# design.net
KiCad netlist of a schematic drawn in EasyEDA Pro
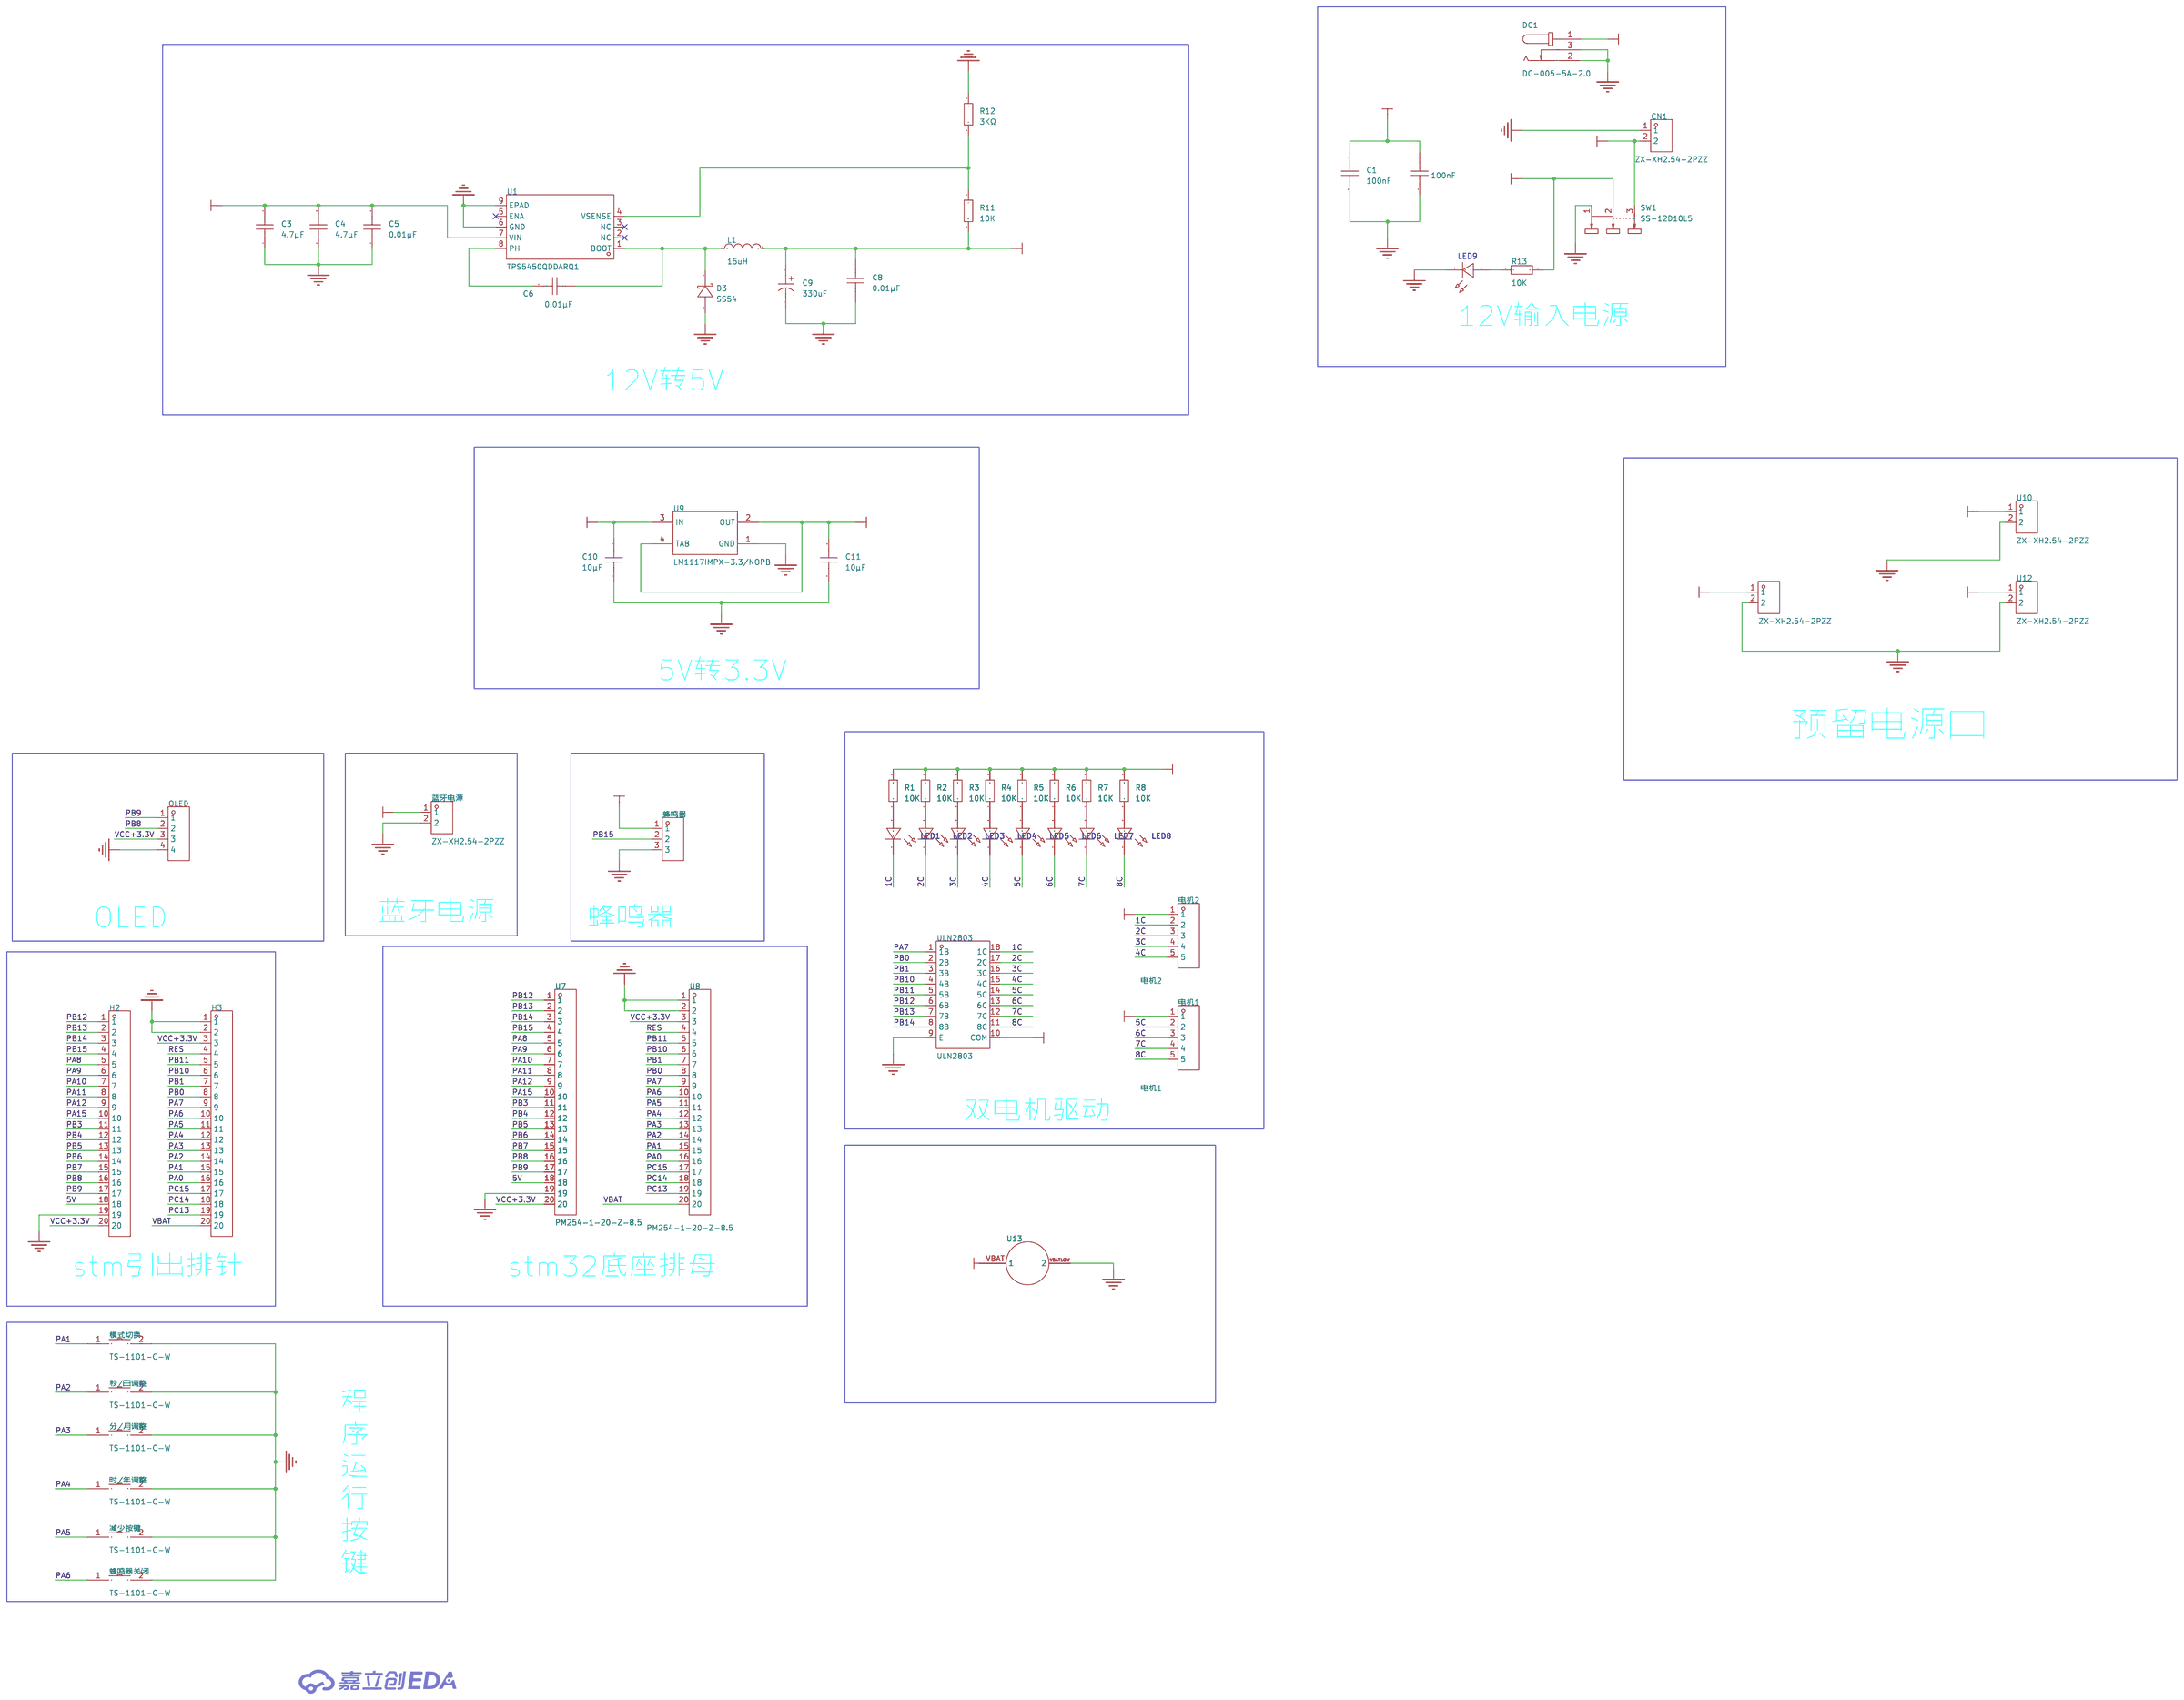
[diagram p0: schematic sheet]

(export (version "E")
  (design (tool "Eeschema 10.0.6"))
  (components
    (comp (ref "C1")
      (value "100nF")
      (footprint "easyedapro:C0603")
      (libsource (lib "easyedapro") (part "CapAcitance"))
    )
    (comp (ref "C2")
      (value "100nF")
      (footprint "easyedapro:C0603")
      (libsource (lib "easyedapro") (part "CapAcitance"))
    )
    (comp (ref "C3")
      (value "4.7μF")
      (footprint "easyedapro:C0603")
      (libsource (lib "easyedapro") (part "CapAcitance"))
    )
    (comp (ref "C4")
      (value "4.7μF")
      (footprint "easyedapro:C0603")
      (libsource (lib "easyedapro") (part "CapAcitance"))
    )
    (comp (ref "C5")
      (value "0.01μF")
      (footprint "easyedapro:C0603")
      (libsource (lib "easyedapro") (part "CapAcitance"))
    )
    (comp (ref "C6")
      (value "0.01μF")
      (footprint "easyedapro:C0603")
      (libsource (lib "easyedapro") (part "CapAcitance"))
    )
    (comp (ref "C8")
      (value "0.01μF")
      (footprint "easyedapro:C0603")
      (libsource (lib "easyedapro") (part "CapAcitance"))
    )
    (comp (ref "C9")
      (value "330uF")
      (footprint "easyedapro:CAP-SMD_BD6.3-L6.6-W6.6-LS7.3-FD")
      (description "容值:330uF;精度:±20%;额定电压:25V;")
      (fields (field (name "Manufacturer Part") "GVM1E331M0607") (field (name "Manufacturer") "HONOR(荣誉)"))
      (libsource (lib "easyedapro") (part "GVM1E331M0607"))
    )
    (comp (ref "C10")
      (value "10μF")
      (footprint "easyedapro:C0603")
      (libsource (lib "easyedapro") (part "CapAcitance"))
    )
    (comp (ref "C11")
      (value "10μF")
      (footprint "easyedapro:C0603")
      (libsource (lib "easyedapro") (part "CapAcitance"))
    )
    (comp (ref "CN1")
      (value "ZX-XH2.54-2PZZ")
      (footprint "easyedapro:CONN-TH_2P-P2.50_HX25003-2A")
      (fields (field (name "Manufacturer") "Megastar(兆星)"))
      (libsource (lib "easyedapro") (part "ZX-XH2.54-2PZZ"))
    )
    (comp (ref "D3")
      (value "SS54")
      (footprint "easyedapro:SMA_L4.3-W2.6-LS5.0-FD")
      (description "二极管配置:独立式;正向压降(Vf):550mV@5.0A;直流反向耐压(Vr):40V;整流电流:5A;")
      (fields (field (name "Manufacturer") "宏迦橙"))
      (libsource (lib "easyedapro") (part "SS54_C7420369"))
    )
    (comp (ref "DC1")
      (value "DC-005-5A-2.0")
      (footprint "easyedapro:DC-IN-TH_DC-005-5A-2.0")
      (description "连接器类型:DC电源插座;安装方式:弯插;触点内径:2mm;触点外径:6.2mm;额定电流:5A;额定电压:24V;工作温度范围:-20°C~+70°C;")
      (fields (field (name "Manufacturer") "XKB Connection(中国星坤)"))
      (libsource (lib "easyedapro") (part "DC-005-5A-2.0"))
    )
    (comp (ref "H2")
      (value "~")
      (footprint "easyedapro:HDR-TH_20P-P2.54-V-M-1")
      (libsource (lib "easyedapro") (part "HDR_2.54-1x20P"))
    )
    (comp (ref "H3")
      (value "~")
      (footprint "easyedapro:HDR-TH_20P-P2.54-V-M-1")
      (libsource (lib "easyedapro") (part "HDR_2.54-1x20P"))
    )
    (comp (ref "L1")
      (value "15uH")
      (footprint "easyedapro:IND-SMD_L7.0-W6.6_FXL0630")
      (description "电感值:15uH;精度:±20%;额定电流:3A;饱和电流(Isat):4.5A;类型:一体成型电感;")
      (fields (field (name "Manufacturer Part") "FXL0630-150-M") (field (name "Manufacturer") "cjiang(长江微电)"))
      (libsource (lib "easyedapro") (part "FXL0630-150-M"))
    )
    (comp (ref "LED1")
      (value "~")
      (footprint "easyedapro:LED_0603")
      (libsource (lib "easyedapro") (part "LED_G"))
    )
    (comp (ref "LED2")
      (value "~")
      (footprint "easyedapro:LED_0603")
      (libsource (lib "easyedapro") (part "LED_G"))
    )
    (comp (ref "LED3")
      (value "~")
      (footprint "easyedapro:LED_0603")
      (libsource (lib "easyedapro") (part "LED_G"))
    )
    (comp (ref "LED4")
      (value "~")
      (footprint "easyedapro:LED_0603")
      (libsource (lib "easyedapro") (part "LED_G"))
    )
    (comp (ref "LED5")
      (value "~")
      (footprint "easyedapro:LED_0603")
      (libsource (lib "easyedapro") (part "LED_G"))
    )
    (comp (ref "LED6")
      (value "~")
      (footprint "easyedapro:LED_0603")
      (libsource (lib "easyedapro") (part "LED_G"))
    )
    (comp (ref "LED7")
      (value "~")
      (footprint "easyedapro:LED_0603")
      (libsource (lib "easyedapro") (part "LED_G"))
    )
    (comp (ref "LED8")
      (value "~")
      (footprint "easyedapro:LED_0603")
      (libsource (lib "easyedapro") (part "LED_G"))
    )
    (comp (ref "LED9")
      (value "~")
      (footprint "easyedapro:LED_0603")
      (libsource (lib "easyedapro") (part "LED_G"))
    )
    (comp (ref "OLED")
      (value "~")
      (footprint "easyedapro:HDR-TH_4P-P2.54-V-F")
      (libsource (lib "easyedapro") (part "2.54-1*4P母"))
    )
    (comp (ref "R1") (value "10K") (footprint "easyedapro:R0603") (libsource (lib "easyedapro") (part "电阻")))
    (comp (ref "R2") (value "10K") (footprint "easyedapro:R0603") (libsource (lib "easyedapro") (part "电阻")))
    (comp (ref "R3") (value "10K") (footprint "easyedapro:R0603") (libsource (lib "easyedapro") (part "电阻")))
    (comp (ref "R4") (value "10K") (footprint "easyedapro:R0603") (libsource (lib "easyedapro") (part "电阻")))
    (comp (ref "R5") (value "10K") (footprint "easyedapro:R0603") (libsource (lib "easyedapro") (part "电阻")))
    (comp (ref "R6") (value "10K") (footprint "easyedapro:R0603") (libsource (lib "easyedapro") (part "电阻")))
    (comp (ref "R7") (value "10K") (footprint "easyedapro:R0603") (libsource (lib "easyedapro") (part "电阻")))
    (comp (ref "R8") (value "10K") (footprint "easyedapro:R0603") (libsource (lib "easyedapro") (part "电阻")))
    (comp (ref "R11") (value "10K") (footprint "easyedapro:R0603") (libsource (lib "easyedapro") (part "电阻")))
    (comp (ref "R12") (value "3KΩ") (footprint "easyedapro:R0603") (libsource (lib "easyedapro") (part "电阻")))
    (comp (ref "R13") (value "10K") (footprint "easyedapro:R0603") (libsource (lib "easyedapro") (part "电阻")))
    (comp (ref "SW1")
      (value "SS-12D10L5")
      (footprint "easyedapro:SW-TH_SS-12D10L5")
      (description "电路结构:单刀双掷;安装方式:直插;开关颜色:黑色;额定电流(DC):3A;额定电压(DC):125V;额定电流(AC):3A;额定电压(AC):125V;机械寿命:1万次;")
      (fields (field (name "Manufacturer") "XKB Connectivity(中国星坤)"))
      (libsource (lib "easyedapro") (part "SS-12D10L5"))
    )
    (comp (ref "U1")
      (value "TPS5450QDDARQ1")
      (footprint "easyedapro:SOIC-8_L4.9-W3.9-P1.27-LS6.0-BL-EP")
      (description "功能类型:降压型;输出类型:可调;工作电压:5.5V~36V;输出电压:1.221V~32.04V;输出电流:5A;")
      (fields (field (name "Manufacturer") "TI(德州仪器)"))
      (libsource (lib "easyedapro") (part "TPS5450QDDARQ1"))
    )
    (comp (ref "U7")
      (value "PM254-1-20-Z-8.5")
      (footprint "easyedapro:HDR-TH_20P-P2.54-V-F-2")
      (fields (field (name "Manufacturer") "HCTL(华灿天禄)"))
      (libsource (lib "easyedapro") (part "PM254-1-20-Z-8.5"))
    )
    (comp (ref "U8")
      (value "PM254-1-20-Z-8.5")
      (footprint "easyedapro:HDR-TH_20P-P2.54-V-F-2")
      (fields (field (name "Manufacturer") "HCTL(华灿天禄)"))
      (libsource (lib "easyedapro") (part "PM254-1-20-Z-8.5"))
    )
    (comp (ref "U9")
      (value "LM1117IMPX-3.3/NOPB")
      (footprint "easyedapro:SOT-223_L6.5-W3.5-P2.30-LS7.0-BR")
      (description "输出类型:固定;最大输入电压:15V;输出电压:3.3V;最大输出电流:800mA;电源纹波抑制比(PSRR):75dB@(120Hz);输出极性:正极;")
      (fields (field (name "Manufacturer") "TI(德州仪器)"))
      (libsource (lib "easyedapro") (part "LM1117IMPX-3.3/NOPB"))
    )
    (comp (ref "U10")
      (value "ZX-XH2.54-2PZZ")
      (footprint "easyedapro:CONN-TH_2P-P2.50_HX25003-2A")
      (fields (field (name "Manufacturer") "Megastar(兆星)"))
      (libsource (lib "easyedapro") (part "ZX-XH2.54-2PZZ"))
    )
    (comp (ref "U11")
      (value "ZX-XH2.54-2PZZ")
      (footprint "easyedapro:CONN-TH_2P-P2.50_HX25003-2A")
      (fields (field (name "Manufacturer") "Megastar(兆星)"))
      (libsource (lib "easyedapro") (part "ZX-XH2.54-2PZZ"))
    )
    (comp (ref "U12")
      (value "ZX-XH2.54-2PZZ")
      (footprint "easyedapro:CONN-TH_2P-P2.50_HX25003-2A")
      (fields (field (name "Manufacturer") "Megastar(兆星)"))
      (libsource (lib "easyedapro") (part "ZX-XH2.54-2PZZ"))
    )
    (comp (ref "U13") (value "~") (libsource (lib "easyedapro") (part "纽扣")))
    (comp (ref "ULN2803")
      (value "ULN2803")
      (footprint "easyedapro:SOP-18_L11.6-W7.5-P1.27-LS10.3-BL")
      (description "通道数:八路;集射击穿电压(Vceo):50V;集电极电流(Ic):500mA;")
      (fields (field (name "Manufacturer") "Siproin(上海矽朋)"))
      (libsource (lib "easyedapro") (part "ULN2803_C2758014"))
    )
    (comp (ref "减少按键")
      (value "TS-1101-C-W")
      (footprint "easyedapro:SW-SMD_L6.0-W3.3-LS8.0")
      (fields (field (name "Manufacturer") "XKB Connectivity(中国星坤)"))
      (libsource (lib "easyedapro") (part "TS-1101-C-W"))
    )
    (comp (ref "分/月调整")
      (value "TS-1101-C-W")
      (footprint "easyedapro:SW-SMD_L6.0-W3.3-LS8.0")
      (fields (field (name "Manufacturer") "XKB Connectivity(中国星坤)"))
      (libsource (lib "easyedapro") (part "TS-1101-C-W"))
    )
    (comp (ref "时/年调整")
      (value "TS-1101-C-W")
      (footprint "easyedapro:SW-SMD_L6.0-W3.3-LS8.0")
      (fields (field (name "Manufacturer") "XKB Connectivity(中国星坤)"))
      (libsource (lib "easyedapro") (part "TS-1101-C-W"))
    )
    (comp (ref "模式切换")
      (value "TS-1101-C-W")
      (footprint "easyedapro:SW-SMD_L6.0-W3.3-LS8.0")
      (fields (field (name "Manufacturer") "XKB Connectivity(中国星坤)"))
      (libsource (lib "easyedapro") (part "TS-1101-C-W"))
    )
    (comp (ref "电机1")
      (value "电机1")
      (footprint "easyedapro:CONN-TH_5P-P2.50_ZX-XH2.54-5PZZ")
      (fields (field (name "Manufacturer") "Megastar(兆星)"))
      (libsource (lib "easyedapro") (part "ZX-XH2.54-5PZZ"))
    )
    (comp (ref "电机2")
      (value "电机2")
      (footprint "easyedapro:CONN-TH_5P-P2.50_ZX-XH2.54-5PZZ")
      (fields (field (name "Manufacturer") "Megastar(兆星)"))
      (libsource (lib "easyedapro") (part "ZX-XH2.54-5PZZ"))
    )
    (comp (ref "秒/日调整")
      (value "TS-1101-C-W")
      (footprint "easyedapro:SW-SMD_L6.0-W3.3-LS8.0")
      (fields (field (name "Manufacturer") "XKB Connectivity(中国星坤)"))
      (libsource (lib "easyedapro") (part "TS-1101-C-W"))
    )
    (comp (ref "蓝牙电源")
      (value "ZX-XH2.54-2PZZ")
      (footprint "easyedapro:CONN-TH_2P-P2.50_HX25003-2A")
      (fields (field (name "Manufacturer") "Megastar(兆星)"))
      (libsource (lib "easyedapro") (part "ZX-XH2.54-2PZZ"))
    )
    (comp (ref "蜂鸣器")
      (value "~")
      (footprint "easyedapro:HDR-TH_3P-P2.54-V-F")
      (libsource (lib "easyedapro") (part "PM254V-11-03-H85"))
    )
    (comp (ref "蜂鸣器关闭")
      (value "TS-1101-C-W")
      (footprint "easyedapro:SW-SMD_L6.0-W3.3-LS8.0")
      (fields (field (name "Manufacturer") "XKB Connectivity(中国星坤)"))
      (libsource (lib "easyedapro") (part "TS-1101-C-W"))
    )
  )
  (nets
    (net (code "1") (name "/1C") (class "Default")
      (node (ref "LED1") (pin "1") (pinfunction "C_1") (pintype "input"))
      (node (ref "ULN2803") (pin "18") (pinfunction "1C_18") (pintype "unspecified"))
      (node (ref "电机2") (pin "2") (pinfunction "2_2") (pintype "unspecified"))
    )
    (net (code "2") (name "/2C") (class "Default")
      (node (ref "LED2") (pin "1") (pinfunction "C_1") (pintype "input"))
      (node (ref "ULN2803") (pin "17") (pinfunction "2C_17") (pintype "unspecified"))
      (node (ref "电机2") (pin "3") (pinfunction "3_3") (pintype "unspecified"))
    )
    (net (code "3") (name "/3C") (class "Default")
      (node (ref "LED3") (pin "1") (pinfunction "C_1") (pintype "input"))
      (node (ref "ULN2803") (pin "16") (pinfunction "3C_16") (pintype "unspecified"))
      (node (ref "电机2") (pin "4") (pinfunction "4_4") (pintype "unspecified"))
    )
    (net (code "4") (name "/4C") (class "Default")
      (node (ref "LED4") (pin "1") (pinfunction "C_1") (pintype "input"))
      (node (ref "ULN2803") (pin "15") (pinfunction "4C_15") (pintype "unspecified"))
      (node (ref "电机2") (pin "5") (pinfunction "5_5") (pintype "unspecified"))
    )
    (net (code "5") (name "/5C") (class "Default")
      (node (ref "LED5") (pin "1") (pinfunction "C_1") (pintype "input"))
      (node (ref "ULN2803") (pin "14") (pinfunction "5C_14") (pintype "unspecified"))
      (node (ref "电机1") (pin "2") (pinfunction "2_2") (pintype "unspecified"))
    )
    (net (code "6") (name "/5V") (class "Default")
      (node (ref "H2") (pin "18") (pinfunction "18_18") (pintype "input"))
      (node (ref "U7") (pin "18") (pinfunction "18_18") (pintype "unspecified"))
    )
    (net (code "7") (name "/6C") (class "Default")
      (node (ref "LED6") (pin "1") (pinfunction "C_1") (pintype "input"))
      (node (ref "ULN2803") (pin "13") (pinfunction "6C_13") (pintype "unspecified"))
      (node (ref "电机1") (pin "3") (pinfunction "3_3") (pintype "unspecified"))
    )
    (net (code "8") (name "/7C") (class "Default")
      (node (ref "LED7") (pin "1") (pinfunction "C_1") (pintype "input"))
      (node (ref "ULN2803") (pin "12") (pinfunction "7C_12") (pintype "unspecified"))
      (node (ref "电机1") (pin "4") (pinfunction "4_4") (pintype "unspecified"))
    )
    (net (code "9") (name "/8C") (class "Default")
      (node (ref "LED8") (pin "1") (pinfunction "C_1") (pintype "input"))
      (node (ref "ULN2803") (pin "11") (pinfunction "8C_11") (pintype "unspecified"))
      (node (ref "电机1") (pin "5") (pinfunction "5_5") (pintype "unspecified"))
    )
    (net (code "10") (name "/PA0") (class "Default")
      (node (ref "H3") (pin "16") (pinfunction "16_16") (pintype "input"))
      (node (ref "U8") (pin "16") (pinfunction "16_16") (pintype "unspecified"))
    )
    (net (code "11") (name "/PA1") (class "Default")
      (node (ref "H3") (pin "15") (pinfunction "15_15") (pintype "input"))
      (node (ref "U8") (pin "15") (pinfunction "15_15") (pintype "unspecified"))
      (node (ref "模式切换") (pin "1") (pinfunction "1_1") (pintype "unspecified"))
    )
    (net (code "12") (name "/PA2") (class "Default")
      (node (ref "H3") (pin "14") (pinfunction "14_14") (pintype "input"))
      (node (ref "U8") (pin "14") (pinfunction "14_14") (pintype "unspecified"))
      (node (ref "秒/日调整") (pin "1") (pinfunction "1_1") (pintype "unspecified"))
    )
    (net (code "13") (name "/PA3") (class "Default")
      (node (ref "H3") (pin "13") (pinfunction "13_13") (pintype "input"))
      (node (ref "U8") (pin "13") (pinfunction "13_13") (pintype "unspecified"))
      (node (ref "分/月调整") (pin "1") (pinfunction "1_1") (pintype "unspecified"))
    )
    (net (code "14") (name "/PA4") (class "Default")
      (node (ref "H3") (pin "12") (pinfunction "12_12") (pintype "input"))
      (node (ref "U8") (pin "12") (pinfunction "12_12") (pintype "unspecified"))
      (node (ref "时/年调整") (pin "1") (pinfunction "1_1") (pintype "unspecified"))
    )
    (net (code "15") (name "/PA5") (class "Default")
      (node (ref "H3") (pin "11") (pinfunction "11_11") (pintype "input"))
      (node (ref "U8") (pin "11") (pinfunction "11_11") (pintype "unspecified"))
      (node (ref "减少按键") (pin "1") (pinfunction "1_1") (pintype "unspecified"))
    )
    (net (code "16") (name "/PA6") (class "Default")
      (node (ref "H3") (pin "10") (pinfunction "10_10") (pintype "input"))
      (node (ref "U8") (pin "10") (pinfunction "10_10") (pintype "unspecified"))
      (node (ref "蜂鸣器关闭") (pin "1") (pinfunction "1_1") (pintype "unspecified"))
    )
    (net (code "17") (name "/PA7") (class "Default")
      (node (ref "H3") (pin "9") (pinfunction "9_9") (pintype "input"))
      (node (ref "U8") (pin "9") (pinfunction "9_9") (pintype "unspecified"))
      (node (ref "ULN2803") (pin "1") (pinfunction "1B_1") (pintype "unspecified"))
    )
    (net (code "18") (name "/PA8") (class "Default")
      (node (ref "H2") (pin "5") (pinfunction "5_5") (pintype "input"))
      (node (ref "U7") (pin "5") (pinfunction "5_5") (pintype "unspecified"))
    )
    (net (code "19") (name "/PA9") (class "Default")
      (node (ref "H2") (pin "6") (pinfunction "6_6") (pintype "input"))
      (node (ref "U7") (pin "6") (pinfunction "6_6") (pintype "unspecified"))
    )
    (net (code "20") (name "/PA10") (class "Default")
      (node (ref "H2") (pin "7") (pinfunction "7_7") (pintype "input"))
      (node (ref "U7") (pin "7") (pinfunction "7_7") (pintype "unspecified"))
    )
    (net (code "21") (name "/PA11") (class "Default")
      (node (ref "H2") (pin "8") (pinfunction "8_8") (pintype "input"))
      (node (ref "U7") (pin "8") (pinfunction "8_8") (pintype "unspecified"))
    )
    (net (code "22") (name "/PA12") (class "Default")
      (node (ref "H2") (pin "9") (pinfunction "9_9") (pintype "input"))
      (node (ref "U7") (pin "9") (pinfunction "9_9") (pintype "unspecified"))
    )
    (net (code "23") (name "/PA15") (class "Default")
      (node (ref "H2") (pin "10") (pinfunction "10_10") (pintype "input"))
      (node (ref "U7") (pin "10") (pinfunction "10_10") (pintype "unspecified"))
    )
    (net (code "24") (name "/PB0") (class "Default")
      (node (ref "H3") (pin "8") (pinfunction "8_8") (pintype "input"))
      (node (ref "U8") (pin "8") (pinfunction "8_8") (pintype "unspecified"))
      (node (ref "ULN2803") (pin "2") (pinfunction "2B_2") (pintype "unspecified"))
    )
    (net (code "25") (name "/PB1") (class "Default")
      (node (ref "H3") (pin "7") (pinfunction "7_7") (pintype "input"))
      (node (ref "U8") (pin "7") (pinfunction "7_7") (pintype "unspecified"))
      (node (ref "ULN2803") (pin "3") (pinfunction "3B_3") (pintype "unspecified"))
    )
    (net (code "26") (name "/PB3") (class "Default")
      (node (ref "H2") (pin "11") (pinfunction "11_11") (pintype "input"))
      (node (ref "U7") (pin "11") (pinfunction "11_11") (pintype "unspecified"))
    )
    (net (code "27") (name "/PB4") (class "Default")
      (node (ref "H2") (pin "12") (pinfunction "12_12") (pintype "input"))
      (node (ref "U7") (pin "12") (pinfunction "12_12") (pintype "unspecified"))
    )
    (net (code "28") (name "/PB5") (class "Default")
      (node (ref "H2") (pin "13") (pinfunction "13_13") (pintype "input"))
      (node (ref "U7") (pin "13") (pinfunction "13_13") (pintype "unspecified"))
    )
    (net (code "29") (name "/PB6") (class "Default")
      (node (ref "H2") (pin "14") (pinfunction "14_14") (pintype "input"))
      (node (ref "U7") (pin "14") (pinfunction "14_14") (pintype "unspecified"))
    )
    (net (code "30") (name "/PB7") (class "Default")
      (node (ref "H2") (pin "15") (pinfunction "15_15") (pintype "input"))
      (node (ref "U7") (pin "15") (pinfunction "15_15") (pintype "unspecified"))
    )
    (net (code "31") (name "/PB8") (class "Default")
      (node (ref "H2") (pin "16") (pinfunction "16_16") (pintype "input"))
      (node (ref "OLED") (pin "2") (pinfunction "2_2") (pintype "unspecified"))
      (node (ref "U7") (pin "16") (pinfunction "16_16") (pintype "unspecified"))
    )
    (net (code "32") (name "/PB9") (class "Default")
      (node (ref "H2") (pin "17") (pinfunction "17_17") (pintype "input"))
      (node (ref "OLED") (pin "1") (pinfunction "1_1") (pintype "unspecified"))
      (node (ref "U7") (pin "17") (pinfunction "17_17") (pintype "unspecified"))
    )
    (net (code "33") (name "/PB10") (class "Default")
      (node (ref "H3") (pin "6") (pinfunction "6_6") (pintype "input"))
      (node (ref "U8") (pin "6") (pinfunction "6_6") (pintype "unspecified"))
      (node (ref "ULN2803") (pin "4") (pinfunction "4B_4") (pintype "unspecified"))
    )
    (net (code "34") (name "/PB11") (class "Default")
      (node (ref "H3") (pin "5") (pinfunction "5_5") (pintype "input"))
      (node (ref "U8") (pin "5") (pinfunction "5_5") (pintype "unspecified"))
      (node (ref "ULN2803") (pin "5") (pinfunction "5B_5") (pintype "unspecified"))
    )
    (net (code "35") (name "/PB12") (class "Default")
      (node (ref "H2") (pin "1") (pinfunction "1_1") (pintype "input"))
      (node (ref "U7") (pin "1") (pinfunction "1_1") (pintype "unspecified"))
      (node (ref "ULN2803") (pin "6") (pinfunction "6B_6") (pintype "unspecified"))
    )
    (net (code "36") (name "/PB13") (class "Default")
      (node (ref "H2") (pin "2") (pinfunction "2_2") (pintype "input"))
      (node (ref "U7") (pin "2") (pinfunction "2_2") (pintype "unspecified"))
      (node (ref "ULN2803") (pin "7") (pinfunction "7B_7") (pintype "unspecified"))
    )
    (net (code "37") (name "/PB14") (class "Default")
      (node (ref "H2") (pin "3") (pinfunction "3_3") (pintype "input"))
      (node (ref "U7") (pin "3") (pinfunction "3_3") (pintype "unspecified"))
      (node (ref "ULN2803") (pin "8") (pinfunction "8B_8") (pintype "unspecified"))
    )
    (net (code "38") (name "/PB15") (class "Default")
      (node (ref "H2") (pin "4") (pinfunction "4_4") (pintype "input"))
      (node (ref "U7") (pin "4") (pinfunction "4_4") (pintype "unspecified"))
      (node (ref "蜂鸣器") (pin "2") (pinfunction "2_2") (pintype "unspecified"))
    )
    (net (code "39") (name "/PC13") (class "Default")
      (node (ref "H3") (pin "19") (pinfunction "19_19") (pintype "input"))
      (node (ref "U8") (pin "19") (pinfunction "19_19") (pintype "unspecified"))
    )
    (net (code "40") (name "/PC14") (class "Default")
      (node (ref "H3") (pin "18") (pinfunction "18_18") (pintype "input"))
      (node (ref "U8") (pin "18") (pinfunction "18_18") (pintype "unspecified"))
    )
    (net (code "41") (name "/PC15") (class "Default")
      (node (ref "H3") (pin "17") (pinfunction "17_17") (pintype "input"))
      (node (ref "U8") (pin "17") (pinfunction "17_17") (pintype "unspecified"))
    )
    (net (code "42") (name "/RES") (class "Default")
      (node (ref "H3") (pin "4") (pinfunction "4_4") (pintype "input"))
      (node (ref "U8") (pin "4") (pinfunction "4_4") (pintype "unspecified"))
    )
    (net (code "43") (name "GND") (class "Default")
      (node (ref "C1") (pin "2") (pinfunction "2_2") (pintype "input"))
      (node (ref "C10") (pin "2") (pinfunction "2_2") (pintype "input"))
      (node (ref "C11") (pin "1") (pinfunction "1_1") (pintype "input"))
      (node (ref "C2") (pin "2") (pinfunction "2_2") (pintype "input"))
      (node (ref "C3") (pin "1") (pinfunction "1_1") (pintype "input"))
      (node (ref "C4") (pin "1") (pinfunction "1_1") (pintype "input"))
      (node (ref "C5") (pin "1") (pinfunction "1_1") (pintype "input"))
      (node (ref "C8") (pin "1") (pinfunction "1_1") (pintype "input"))
      (node (ref "C9") (pin "2") (pinfunction "2_2") (pintype "input"))
      (node (ref "CN1") (pin "1") (pinfunction "1_1") (pintype "unspecified"))
      (node (ref "D3") (pin "1") (pinfunction "A_1") (pintype "unspecified"))
      (node (ref "DC1") (pin "2") (pinfunction "2_2") (pintype "unspecified"))
      (node (ref "DC1") (pin "3") (pinfunction "3_3") (pintype "unspecified"))
      (node (ref "H2") (pin "19") (pinfunction "19_19") (pintype "input"))
      (node (ref "H3") (pin "1") (pinfunction "1_1") (pintype "input"))
      (node (ref "H3") (pin "2") (pinfunction "2_2") (pintype "input"))
      (node (ref "LED9") (pin "1") (pinfunction "C_1") (pintype "input"))
      (node (ref "OLED") (pin "4") (pinfunction "4_4") (pintype "unspecified"))
      (node (ref "R12") (pin "1") (pinfunction "1_1") (pintype "input"))
      (node (ref "SW1") (pin "1") (pinfunction "1_1") (pintype "unspecified"))
      (node (ref "U1") (pin "6") (pinfunction "GND_6") (pintype "unspecified"))
      (node (ref "U1") (pin "9") (pinfunction "EPAD_9") (pintype "unspecified"))
      (node (ref "U10") (pin "2") (pinfunction "2_2") (pintype "unspecified"))
      (node (ref "U11") (pin "2") (pinfunction "2_2") (pintype "unspecified"))
      (node (ref "U12") (pin "2") (pinfunction "2_2") (pintype "unspecified"))
      (node (ref "U13") (pin "VBATLOW") (pinfunction "2_VBATLOW") (pintype "input"))
      (node (ref "U7") (pin "19") (pinfunction "19_19") (pintype "unspecified"))
      (node (ref "U8") (pin "1") (pinfunction "1_1") (pintype "unspecified"))
      (node (ref "U8") (pin "2") (pinfunction "2_2") (pintype "unspecified"))
      (node (ref "U9") (pin "1") (pinfunction "GND_1") (pintype "unspecified"))
      (node (ref "ULN2803") (pin "9") (pinfunction "E_9") (pintype "unspecified"))
      (node (ref "减少按键") (pin "2") (pinfunction "2_2") (pintype "unspecified"))
      (node (ref "分/月调整") (pin "2") (pinfunction "2_2") (pintype "unspecified"))
      (node (ref "时/年调整") (pin "2") (pinfunction "2_2") (pintype "unspecified"))
      (node (ref "模式切换") (pin "2") (pinfunction "2_2") (pintype "unspecified"))
      (node (ref "秒/日调整") (pin "2") (pinfunction "2_2") (pintype "unspecified"))
      (node (ref "蓝牙电源") (pin "2") (pinfunction "2_2") (pintype "unspecified"))
      (node (ref "蜂鸣器") (pin "3") (pinfunction "3_3") (pintype "unspecified"))
      (node (ref "蜂鸣器关闭") (pin "2") (pinfunction "2_2") (pintype "unspecified"))
    )
    (net (code "44") (name "Net-(D3-K)") (class "Default")
      (node (ref "C6") (pin "2") (pinfunction "2_2") (pintype "input"))
      (node (ref "D3") (pin "2") (pinfunction "K_2") (pintype "unspecified"))
      (node (ref "L1") (pin "1") (pinfunction "1_1") (pintype "unspecified"))
      (node (ref "U1") (pin "1") (pinfunction "BOOT_1") (pintype "unspecified"))
    )
    (net (code "45") (name "Net-(LED1-A)") (class "Default")
      (node (ref "LED1") (pin "2") (pinfunction "A_2") (pintype "input"))
      (node (ref "R1") (pin "1") (pinfunction "1_1") (pintype "input"))
    )
    (net (code "46") (name "Net-(LED2-A)") (class "Default")
      (node (ref "LED2") (pin "2") (pinfunction "A_2") (pintype "input"))
      (node (ref "R2") (pin "1") (pinfunction "1_1") (pintype "input"))
    )
    (net (code "47") (name "Net-(LED3-A)") (class "Default")
      (node (ref "LED3") (pin "2") (pinfunction "A_2") (pintype "input"))
      (node (ref "R3") (pin "1") (pinfunction "1_1") (pintype "input"))
    )
    (net (code "48") (name "Net-(LED4-A)") (class "Default")
      (node (ref "LED4") (pin "2") (pinfunction "A_2") (pintype "input"))
      (node (ref "R4") (pin "1") (pinfunction "1_1") (pintype "input"))
    )
    (net (code "49") (name "Net-(LED5-A)") (class "Default")
      (node (ref "LED5") (pin "2") (pinfunction "A_2") (pintype "input"))
      (node (ref "R5") (pin "1") (pinfunction "1_1") (pintype "input"))
    )
    (net (code "50") (name "Net-(LED6-A)") (class "Default")
      (node (ref "LED6") (pin "2") (pinfunction "A_2") (pintype "input"))
      (node (ref "R6") (pin "1") (pinfunction "1_1") (pintype "input"))
    )
    (net (code "51") (name "Net-(LED7-A)") (class "Default")
      (node (ref "LED7") (pin "2") (pinfunction "A_2") (pintype "input"))
      (node (ref "R7") (pin "1") (pinfunction "1_1") (pintype "input"))
    )
    (net (code "52") (name "Net-(LED8-A)") (class "Default")
      (node (ref "LED8") (pin "2") (pinfunction "A_2") (pintype "input"))
      (node (ref "R8") (pin "1") (pinfunction "1_1") (pintype "input"))
    )
    (net (code "53") (name "Net-(LED9-A)") (class "Default")
      (node (ref "LED9") (pin "2") (pinfunction "A_2") (pintype "input"))
      (node (ref "R13") (pin "1") (pinfunction "1_1") (pintype "input"))
    )
    (net (code "54") (name "Net-(U1-PH)") (class "Default")
      (node (ref "C6") (pin "1") (pinfunction "1_1") (pintype "input"))
      (node (ref "U1") (pin "8") (pinfunction "PH_8") (pintype "unspecified"))
    )
    (net (code "55") (name "Net-(U1-VSENSE)") (class "Default")
      (node (ref "R11") (pin "1") (pinfunction "1_1") (pintype "input"))
      (node (ref "R12") (pin "2") (pinfunction "2_2") (pintype "input"))
      (node (ref "U1") (pin "4") (pinfunction "VSENSE_4") (pintype "unspecified"))
    )
    (net (code "56") (name "VBAT") (class "Default")
      (node (ref "H3") (pin "20") (pinfunction "20_20") (pintype "input"))
      (node (ref "U13") (pin "VBAT") (pinfunction "1_VBAT") (pintype "input"))
      (node (ref "U8") (pin "20") (pinfunction "20_20") (pintype "unspecified"))
    )
    (net (code "57") (name "VCC+3.3V") (class "Default")
      (node (ref "C11") (pin "2") (pinfunction "2_2") (pintype "input"))
      (node (ref "H2") (pin "20") (pinfunction "20_20") (pintype "input"))
      (node (ref "H3") (pin "3") (pinfunction "3_3") (pintype "input"))
      (node (ref "OLED") (pin "3") (pinfunction "3_3") (pintype "unspecified"))
      (node (ref "U11") (pin "1") (pinfunction "1_1") (pintype "unspecified"))
      (node (ref "U7") (pin "20") (pinfunction "20_20") (pintype "unspecified"))
      (node (ref "U8") (pin "3") (pinfunction "3_3") (pintype "unspecified"))
      (node (ref "U9") (pin "2") (pinfunction "OUT_2") (pintype "unspecified"))
      (node (ref "U9") (pin "4") (pinfunction "TAB_4") (pintype "unspecified"))
      (node (ref "蜂鸣器") (pin "1") (pinfunction "1_1") (pintype "unspecified"))
    )
    (net (code "58") (name "VCC+5V") (class "Default")
      (node (ref "C10") (pin "1") (pinfunction "1_1") (pintype "input"))
      (node (ref "C8") (pin "2") (pinfunction "2_2") (pintype "input"))
      (node (ref "C9") (pin "1") (pinfunction "1_1") (pintype "input"))
      (node (ref "L1") (pin "2") (pinfunction "2_2") (pintype "unspecified"))
      (node (ref "R1") (pin "2") (pinfunction "2_2") (pintype "input"))
      (node (ref "R11") (pin "2") (pinfunction "2_2") (pintype "input"))
      (node (ref "R2") (pin "2") (pinfunction "2_2") (pintype "input"))
      (node (ref "R3") (pin "2") (pinfunction "2_2") (pintype "input"))
      (node (ref "R4") (pin "2") (pinfunction "2_2") (pintype "input"))
      (node (ref "R5") (pin "2") (pinfunction "2_2") (pintype "input"))
      (node (ref "R6") (pin "2") (pinfunction "2_2") (pintype "input"))
      (node (ref "R7") (pin "2") (pinfunction "2_2") (pintype "input"))
      (node (ref "R8") (pin "2") (pinfunction "2_2") (pintype "input"))
      (node (ref "U10") (pin "1") (pinfunction "1_1") (pintype "unspecified"))
      (node (ref "U12") (pin "1") (pinfunction "1_1") (pintype "unspecified"))
      (node (ref "U9") (pin "3") (pinfunction "IN_3") (pintype "unspecified"))
      (node (ref "ULN2803") (pin "10") (pinfunction "COM_10") (pintype "unspecified"))
      (node (ref "电机1") (pin "1") (pinfunction "1_1") (pintype "unspecified"))
      (node (ref "电机2") (pin "1") (pinfunction "1_1") (pintype "unspecified"))
      (node (ref "蓝牙电源") (pin "1") (pinfunction "1_1") (pintype "unspecified"))
    )
    (net (code "59") (name "VCC12V") (class "Default")
      (node (ref "C1") (pin "1") (pinfunction "1_1") (pintype "input"))
      (node (ref "C2") (pin "1") (pinfunction "1_1") (pintype "input"))
      (node (ref "C3") (pin "2") (pinfunction "2_2") (pintype "input"))
      (node (ref "C4") (pin "2") (pinfunction "2_2") (pintype "input"))
      (node (ref "C5") (pin "2") (pinfunction "2_2") (pintype "input"))
      (node (ref "R13") (pin "2") (pinfunction "2_2") (pintype "input"))
      (node (ref "SW1") (pin "2") (pinfunction "2_2") (pintype "unspecified"))
      (node (ref "U1") (pin "7") (pinfunction "VIN_7") (pintype "unspecified"))
    )
    (net (code "60") (name "VIN") (class "Default")
      (node (ref "CN1") (pin "2") (pinfunction "2_2") (pintype "unspecified"))
      (node (ref "DC1") (pin "1") (pinfunction "1_1") (pintype "unspecified"))
      (node (ref "SW1") (pin "3") (pinfunction "3_3") (pintype "unspecified"))
    )
    (net (code "61") (name "unconnected-(U1-ENA-Pad5)") (class "Default")
      (node (ref "U1") (pin "5") (pinfunction "ENA_5") (pintype "unspecified+no_connect"))
    )
    (net (code "62") (name "unconnected-(U1-NC-Pad2)") (class "Default")
      (node (ref "U1") (pin "2") (pinfunction "NC_2") (pintype "unspecified+no_connect"))
    )
    (net (code "63") (name "unconnected-(U1-NC-Pad3)") (class "Default")
      (node (ref "U1") (pin "3") (pinfunction "NC_3") (pintype "unspecified+no_connect"))
    )
  )
)
